# vacbox.net
KiCad netlist of a schematic drawn in EAGLE
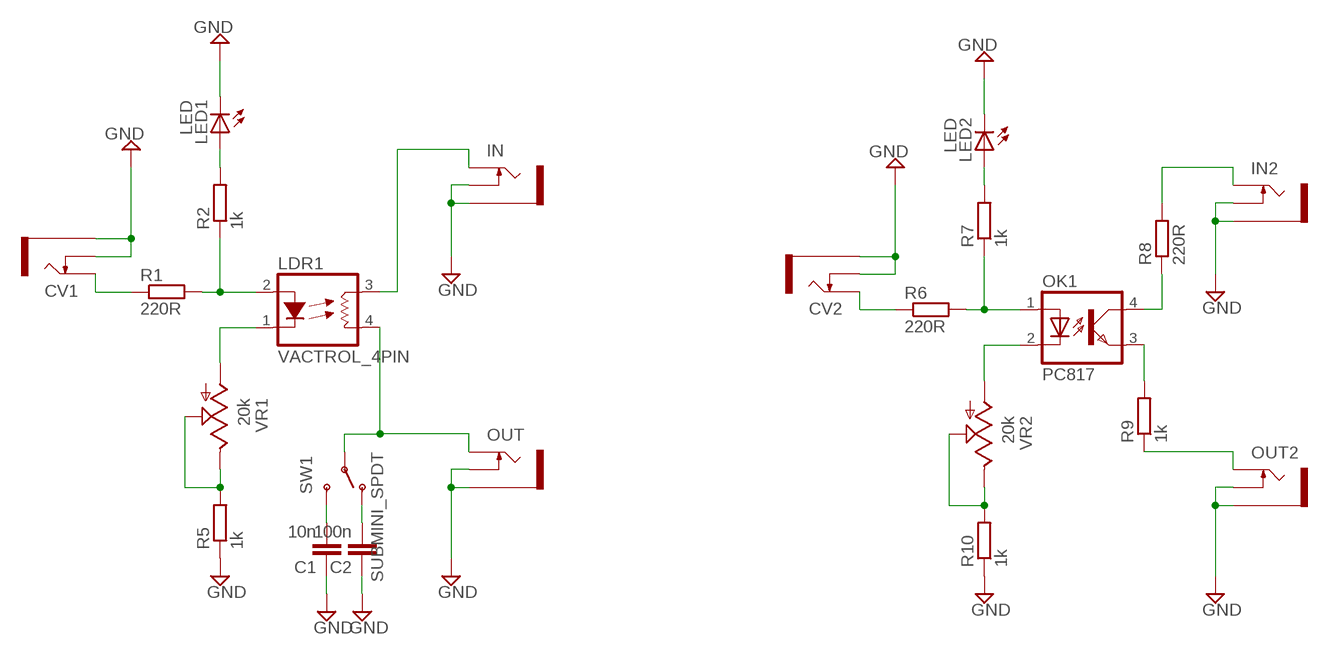
[diagram p0: schematic, sheet 1]

(export (version "E")
  (design (tool "Eeschema 10.0.6"))
  (components
    (comp (ref "C1")
      (value "10n")
      (footprint "eagle-import:C050-025X075")
      (libsource (lib "eagle-import") (part "C-EU050-025X075"))
    )
    (comp (ref "C2")
      (value "100n")
      (footprint "eagle-import:C050-025X075")
      (libsource (lib "eagle-import") (part "C-EU050-025X075"))
    )
    (comp (ref "CV1")
      (value "PJ302M")
      (footprint "eagle-import:PJ302M")
      (libsource (lib "eagle-import") (part "PJ302M"))
    )
    (comp (ref "CV2")
      (value "PJ302M")
      (footprint "eagle-import:PJ302M")
      (libsource (lib "eagle-import") (part "PJ302M"))
    )
    (comp (ref "IN")
      (value "PJ302M")
      (footprint "eagle-import:PJ302M")
      (libsource (lib "eagle-import") (part "PJ302M"))
    )
    (comp (ref "IN2")
      (value "PJ302M")
      (footprint "eagle-import:PJ302M")
      (libsource (lib "eagle-import") (part "PJ302M"))
    )
    (comp (ref "LDR1")
      (value "VACTROL_4PIN")
      (footprint "eagle-import:VACTROL_4PIN_VTL5C")
      (libsource (lib "eagle-import") (part "VACTROL_4PIN"))
    )
    (comp (ref "LED1")
      (value "LED")
      (footprint "eagle-import:LED3MM")
      (libsource (lib "eagle-import") (part "LED3MM"))
    )
    (comp (ref "LED2")
      (value "LED")
      (footprint "eagle-import:LED3MM")
      (libsource (lib "eagle-import") (part "LED3MM"))
    )
    (comp (ref "OK1")
      (value "PC817")
      (footprint "eagle-import:DIL04")
      (fields (field (name "MPN") "PC817X4J000F"))
      (libsource (lib "eagle-import") (part "PC817"))
    )
    (comp (ref "OUT")
      (value "PJ302M")
      (footprint "eagle-import:PJ302M")
      (libsource (lib "eagle-import") (part "PJ302M"))
    )
    (comp (ref "OUT2")
      (value "PJ302M")
      (footprint "eagle-import:PJ302M")
      (libsource (lib "eagle-import") (part "PJ302M"))
    )
    (comp (ref "R1")
      (value "220R")
      (footprint "eagle-import:0207_2V")
      (libsource (lib "eagle-import") (part "R-EU_0207/2V"))
    )
    (comp (ref "R2")
      (value "1k")
      (footprint "eagle-import:0207_2V")
      (libsource (lib "eagle-import") (part "R-EU_0207/2V"))
    )
    (comp (ref "R5")
      (value "1k")
      (footprint "eagle-import:0207_2V")
      (libsource (lib "eagle-import") (part "R-EU_0207/2V"))
    )
    (comp (ref "R6")
      (value "220R")
      (footprint "eagle-import:0207_2V")
      (libsource (lib "eagle-import") (part "R-EU_0207/2V"))
    )
    (comp (ref "R7")
      (value "1k")
      (footprint "eagle-import:0207_2V")
      (libsource (lib "eagle-import") (part "R-EU_0207/2V"))
    )
    (comp (ref "R8")
      (value "220R")
      (footprint "eagle-import:0207_2V")
      (libsource (lib "eagle-import") (part "R-EU_0207/2V"))
    )
    (comp (ref "R9")
      (value "1k")
      (footprint "eagle-import:0207_2V")
      (libsource (lib "eagle-import") (part "R-EU_0207/2V"))
    )
    (comp (ref "R10")
      (value "1k")
      (footprint "eagle-import:0207_2V")
      (libsource (lib "eagle-import") (part "R-EU_0207/2V"))
    )
    (comp (ref "SW1")
      (value "SUBMINI_SPDT")
      (footprint "eagle-import:SUBMINI_TOGGLE")
      (libsource (lib "eagle-import") (part "SUBMINI_SPDT"))
    )
    (comp (ref "VR1")
      (value "20k")
      (footprint "eagle-import:9MM_SNAP-IN_POT")
      (libsource (lib "eagle-import") (part "9MM_SNAP-IN_POT_"))
    )
    (comp (ref "VR2")
      (value "20k")
      (footprint "eagle-import:9MM_SNAP-IN_POT")
      (libsource (lib "eagle-import") (part "9MM_SNAP-IN_POT_"))
    )
  )
  (nets
    (net (code "1") (name "GND") (class "Default")
      (node (ref "C1") (pin "1") (pinfunction "1_1") (pintype "passive"))
      (node (ref "C2") (pin "1") (pinfunction "1_1") (pintype "passive"))
      (node (ref "CV1") (pin "GND") (pinfunction "SLEEVE_GND") (pintype "passive"))
      (node (ref "CV1") (pin "SW") (pinfunction "SWITCH_SW") (pintype "passive"))
      (node (ref "CV2") (pin "GND") (pinfunction "SLEEVE_GND") (pintype "passive"))
      (node (ref "CV2") (pin "SW") (pinfunction "SWITCH_SW") (pintype "passive"))
      (node (ref "IN") (pin "GND") (pinfunction "SLEEVE_GND") (pintype "passive"))
      (node (ref "IN") (pin "SW") (pinfunction "SWITCH_SW") (pintype "passive"))
      (node (ref "IN2") (pin "GND") (pinfunction "SLEEVE_GND") (pintype "passive"))
      (node (ref "IN2") (pin "SW") (pinfunction "SWITCH_SW") (pintype "passive"))
      (node (ref "LED1") (pin "K") (pinfunction "C_K") (pintype "passive"))
      (node (ref "LED2") (pin "K") (pinfunction "C_K") (pintype "passive"))
      (node (ref "OUT") (pin "GND") (pinfunction "SLEEVE_GND") (pintype "passive"))
      (node (ref "OUT") (pin "SW") (pinfunction "SWITCH_SW") (pintype "passive"))
      (node (ref "OUT2") (pin "GND") (pinfunction "SLEEVE_GND") (pintype "passive"))
      (node (ref "OUT2") (pin "SW") (pinfunction "SWITCH_SW") (pintype "passive"))
      (node (ref "R10") (pin "1") (pinfunction "1_1") (pintype "passive"))
      (node (ref "R5") (pin "1") (pinfunction "1_1") (pintype "passive"))
    )
    (net (code "2") (name "Net-(CV1-PadTIP)") (class "Default")
      (node (ref "CV1") (pin "TIP") (pinfunction "TIP_TIP") (pintype "passive"))
      (node (ref "R1") (pin "1") (pinfunction "1_1") (pintype "passive"))
    )
    (net (code "3") (name "Net-(CV2-PadTIP)") (class "Default")
      (node (ref "CV2") (pin "TIP") (pinfunction "TIP_TIP") (pintype "passive"))
      (node (ref "R6") (pin "1") (pinfunction "1_1") (pintype "passive"))
    )
    (net (code "4") (name "Net-(IN2-PadTIP)") (class "Default")
      (node (ref "IN2") (pin "TIP") (pinfunction "TIP_TIP") (pintype "passive"))
      (node (ref "R8") (pin "2") (pinfunction "2_2") (pintype "passive"))
    )
    (net (code "5") (name "Net-(LDR1-LED+)") (class "Default")
      (node (ref "LDR1") (pin "2") (pinfunction "LED+_2") (pintype "passive"))
      (node (ref "R1") (pin "2") (pinfunction "2_2") (pintype "passive"))
      (node (ref "R2") (pin "1") (pinfunction "1_1") (pintype "passive"))
    )
    (net (code "6") (name "Net-(LDR1-LED-)") (class "Default")
      (node (ref "LDR1") (pin "1") (pinfunction "LED-_1") (pintype "passive"))
      (node (ref "VR1") (pin "1") (pinfunction "A_1") (pintype "passive"))
    )
    (net (code "7") (name "Net-(LDR1-RES1)") (class "Default")
      (node (ref "IN") (pin "TIP") (pinfunction "TIP_TIP") (pintype "passive"))
      (node (ref "LDR1") (pin "3") (pinfunction "RES1_3") (pintype "passive"))
    )
    (net (code "8") (name "Net-(LDR1-RES2)") (class "Default")
      (node (ref "LDR1") (pin "4") (pinfunction "RES2_4") (pintype "passive"))
      (node (ref "OUT") (pin "TIP") (pinfunction "TIP_TIP") (pintype "passive"))
      (node (ref "SW1") (pin "COM") (pinfunction "COMMON_COM") (pintype "passive"))
    )
    (net (code "9") (name "Net-(LED1-PadA)") (class "Default")
      (node (ref "LED1") (pin "A") (pinfunction "A_A") (pintype "passive"))
      (node (ref "R2") (pin "2") (pinfunction "2_2") (pintype "passive"))
    )
    (net (code "10") (name "Net-(LED2-PadA)") (class "Default")
      (node (ref "LED2") (pin "A") (pinfunction "A_A") (pintype "passive"))
      (node (ref "R7") (pin "2") (pinfunction "2_2") (pintype "passive"))
    )
    (net (code "11") (name "Net-(OK1-A)") (class "Default")
      (node (ref "OK1") (pin "1") (pinfunction "A_1") (pintype "passive"))
      (node (ref "R6") (pin "2") (pinfunction "2_2") (pintype "passive"))
      (node (ref "R7") (pin "1") (pinfunction "1_1") (pintype "passive"))
    )
    (net (code "12") (name "Net-(OK1-C)") (class "Default")
      (node (ref "OK1") (pin "2") (pinfunction "C_2") (pintype "passive"))
      (node (ref "VR2") (pin "1") (pinfunction "A_1") (pintype "passive"))
    )
    (net (code "13") (name "Net-(OK1-COL)") (class "Default")
      (node (ref "OK1") (pin "4") (pinfunction "COL_4") (pintype "passive"))
      (node (ref "R8") (pin "1") (pinfunction "1_1") (pintype "passive"))
    )
    (net (code "14") (name "Net-(OK1-EMIT)") (class "Default")
      (node (ref "OK1") (pin "3") (pinfunction "EMIT_3") (pintype "passive"))
      (node (ref "R9") (pin "2") (pinfunction "2_2") (pintype "passive"))
    )
    (net (code "15") (name "Net-(OUT2-PadTIP)") (class "Default")
      (node (ref "OUT2") (pin "TIP") (pinfunction "TIP_TIP") (pintype "passive"))
      (node (ref "R9") (pin "1") (pinfunction "1_1") (pintype "passive"))
    )
    (net (code "16") (name "Net-(SW1-O)") (class "Default")
      (node (ref "C2") (pin "2") (pinfunction "2_2") (pintype "passive"))
      (node (ref "SW1") (pin "1") (pinfunction "O_1") (pintype "passive"))
    )
    (net (code "17") (name "Net-(SW1-S)") (class "Default")
      (node (ref "C1") (pin "2") (pinfunction "2_2") (pintype "passive"))
      (node (ref "SW1") (pin "3") (pinfunction "S_3") (pintype "passive"))
    )
    (net (code "18") (name "Net-(VR1-E)") (class "Default")
      (node (ref "R5") (pin "2") (pinfunction "2_2") (pintype "passive"))
      (node (ref "VR1") (pin "2") (pinfunction "S_2") (pintype "passive"))
      (node (ref "VR1") (pin "3") (pinfunction "E_3") (pintype "passive"))
    )
    (net (code "19") (name "Net-(VR2-E)") (class "Default")
      (node (ref "R10") (pin "2") (pinfunction "2_2") (pintype "passive"))
      (node (ref "VR2") (pin "2") (pinfunction "S_2") (pintype "passive"))
      (node (ref "VR2") (pin "3") (pinfunction "E_3") (pintype "passive"))
    )
  )
)
